# 19_DDR3_BOT.net
KiCad netlist of a schematic drawn in Altium Designer
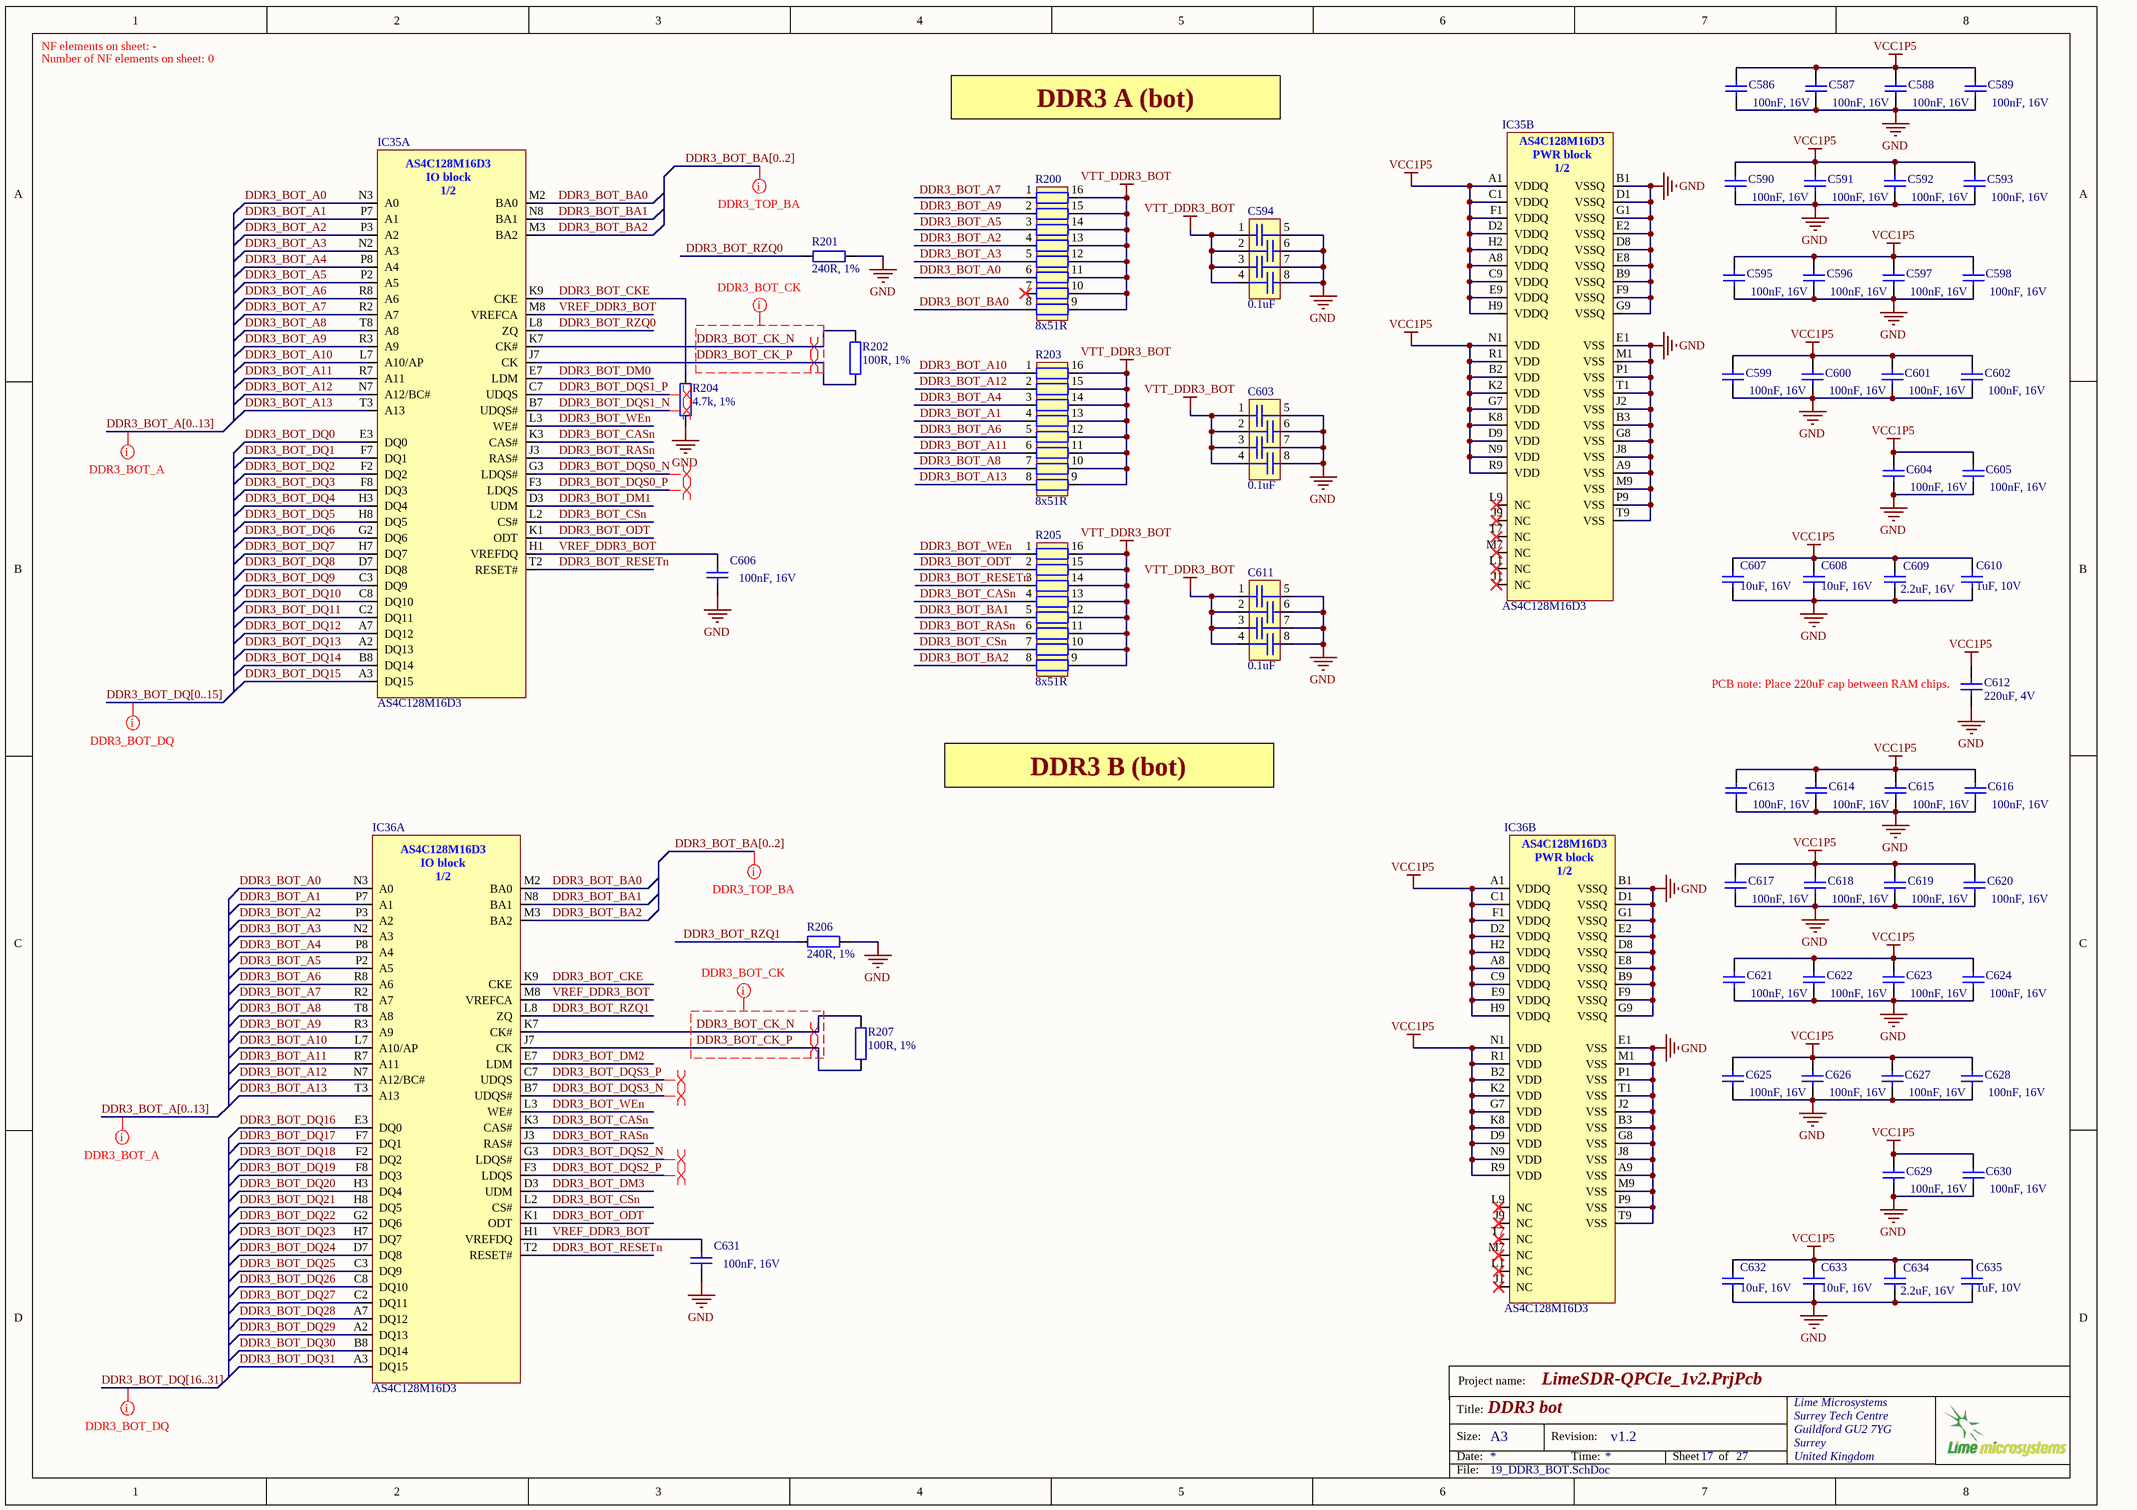
[diagram p0: 19_DDR3_BOT.SchDoc]

(export (version "E")
  (design (tool "Eeschema 10.0.6"))
  (components
    (comp (ref "C586")
      (value "100nF, 16V")
      (footprint "CAP0402")
      (fields
        (field (name "TOLERANCE") "10 %")
        (field (name "MANUFACTURER") "Murata Electronics")
        (field (name "MANUFACTURER PART NUMBER") "GRM155R71C104KA88D")
      )
      (libsource (lib "LimeFPGAboard_schLib") (part "Cap_0603"))
    )
    (comp (ref "C587")
      (value "100nF, 16V")
      (footprint "CAP0402")
      (fields
        (field (name "TOLERANCE") "10 %")
        (field (name "MANUFACTURER") "Murata Electronics")
        (field (name "MANUFACTURER PART NUMBER") "GRM155R71C104KA88D")
      )
      (libsource (lib "LimeFPGAboard_schLib") (part "Cap_0603"))
    )
    (comp (ref "C588")
      (value "100nF, 16V")
      (footprint "CAP0402")
      (fields
        (field (name "TOLERANCE") "10 %")
        (field (name "MANUFACTURER") "Murata Electronics")
        (field (name "MANUFACTURER PART NUMBER") "GRM155R71C104KA88D")
      )
      (libsource (lib "LimeFPGAboard_schLib") (part "Cap_0603"))
    )
    (comp (ref "C589")
      (value "100nF, 16V")
      (footprint "CAP0402")
      (fields
        (field (name "TOLERANCE") "10 %")
        (field (name "MANUFACTURER") "Murata Electronics")
        (field (name "MANUFACTURER PART NUMBER") "GRM155R71C104KA88D")
      )
      (libsource (lib "LimeFPGAboard_schLib") (part "Cap_0603"))
    )
    (comp (ref "C590")
      (value "100nF, 16V")
      (footprint "CAP0402")
      (fields
        (field (name "TOLERANCE") "10 %")
        (field (name "MANUFACTURER") "Murata Electronics")
        (field (name "MANUFACTURER PART NUMBER") "GRM155R71C104KA88D")
      )
      (libsource (lib "LimeFPGAboard_schLib") (part "Cap_0603"))
    )
    (comp (ref "C591")
      (value "100nF, 16V")
      (footprint "CAP0402")
      (fields
        (field (name "TOLERANCE") "10 %")
        (field (name "MANUFACTURER") "Murata Electronics")
        (field (name "MANUFACTURER PART NUMBER") "GRM155R71C104KA88D")
      )
      (libsource (lib "LimeFPGAboard_schLib") (part "Cap_0603"))
    )
    (comp (ref "C592")
      (value "100nF, 16V")
      (footprint "CAP0402")
      (fields
        (field (name "TOLERANCE") "10 %")
        (field (name "MANUFACTURER") "Murata Electronics")
        (field (name "MANUFACTURER PART NUMBER") "GRM155R71C104KA88D")
      )
      (libsource (lib "LimeFPGAboard_schLib") (part "Cap_0603"))
    )
    (comp (ref "C593")
      (value "100nF, 16V")
      (footprint "CAP0402")
      (fields
        (field (name "TOLERANCE") "10 %")
        (field (name "MANUFACTURER") "Murata Electronics")
        (field (name "MANUFACTURER PART NUMBER") "GRM155R71C104KA88D")
      )
      (libsource (lib "LimeFPGAboard_schLib") (part "Cap_0603"))
    )
    (comp (ref "C594")
      (value "0.1uF")
      (footprint "CKCA43X7R1C104M100AA")
      (fields (field (name "MANUFACTURER") "TDK") (field (name "TOLERANCE") "20 %"))
      (libsource (lib "LimeFPGAboard_schLib") (part "4X_cap_array_1206"))
    )
    (comp (ref "C595")
      (value "100nF, 16V")
      (footprint "CAP0402")
      (fields
        (field (name "TOLERANCE") "10 %")
        (field (name "MANUFACTURER") "Murata Electronics")
        (field (name "MANUFACTURER PART NUMBER") "GRM155R71C104KA88D")
      )
      (libsource (lib "LimeFPGAboard_schLib") (part "Cap_0603"))
    )
    (comp (ref "C596")
      (value "100nF, 16V")
      (footprint "CAP0402")
      (fields
        (field (name "TOLERANCE") "10 %")
        (field (name "MANUFACTURER") "Murata Electronics")
        (field (name "MANUFACTURER PART NUMBER") "GRM155R71C104KA88D")
      )
      (libsource (lib "LimeFPGAboard_schLib") (part "Cap_0603"))
    )
    (comp (ref "C597")
      (value "100nF, 16V")
      (footprint "CAP0402")
      (fields
        (field (name "TOLERANCE") "10 %")
        (field (name "MANUFACTURER") "Murata Electronics")
        (field (name "MANUFACTURER PART NUMBER") "GRM155R71C104KA88D")
      )
      (libsource (lib "LimeFPGAboard_schLib") (part "Cap_0603"))
    )
    (comp (ref "C598")
      (value "100nF, 16V")
      (footprint "CAP0402")
      (fields
        (field (name "TOLERANCE") "10 %")
        (field (name "MANUFACTURER") "Murata Electronics")
        (field (name "MANUFACTURER PART NUMBER") "GRM155R71C104KA88D")
      )
      (libsource (lib "LimeFPGAboard_schLib") (part "Cap_0603"))
    )
    (comp (ref "C599")
      (value "100nF, 16V")
      (footprint "CAP0402")
      (fields
        (field (name "TOLERANCE") "10 %")
        (field (name "MANUFACTURER") "Murata Electronics")
        (field (name "MANUFACTURER PART NUMBER") "GRM155R71C104KA88D")
      )
      (libsource (lib "LimeFPGAboard_schLib") (part "Cap_0603"))
    )
    (comp (ref "C600")
      (value "100nF, 16V")
      (footprint "CAP0402")
      (fields
        (field (name "TOLERANCE") "10 %")
        (field (name "MANUFACTURER") "Murata Electronics")
        (field (name "MANUFACTURER PART NUMBER") "GRM155R71C104KA88D")
      )
      (libsource (lib "LimeFPGAboard_schLib") (part "Cap_0603"))
    )
    (comp (ref "C601")
      (value "100nF, 16V")
      (footprint "CAP0402")
      (fields
        (field (name "TOLERANCE") "10 %")
        (field (name "MANUFACTURER") "Murata Electronics")
        (field (name "MANUFACTURER PART NUMBER") "GRM155R71C104KA88D")
      )
      (libsource (lib "LimeFPGAboard_schLib") (part "Cap_0603"))
    )
    (comp (ref "C602")
      (value "100nF, 16V")
      (footprint "CAP0402")
      (fields
        (field (name "TOLERANCE") "10 %")
        (field (name "MANUFACTURER") "Murata Electronics")
        (field (name "MANUFACTURER PART NUMBER") "GRM155R71C104KA88D")
      )
      (libsource (lib "LimeFPGAboard_schLib") (part "Cap_0603"))
    )
    (comp (ref "C603")
      (value "0.1uF")
      (footprint "CKCA43X7R1C104M100AA")
      (fields (field (name "MANUFACTURER") "TDK") (field (name "TOLERANCE") "20 %"))
      (libsource (lib "LimeFPGAboard_schLib") (part "4X_cap_array_1206"))
    )
    (comp (ref "C604")
      (value "100nF, 16V")
      (footprint "CAP0402")
      (fields
        (field (name "TOLERANCE") "10 %")
        (field (name "MANUFACTURER") "Murata Electronics")
        (field (name "MANUFACTURER PART NUMBER") "GRM155R71C104KA88D")
      )
      (libsource (lib "LimeFPGAboard_schLib") (part "Cap_0603"))
    )
    (comp (ref "C605")
      (value "100nF, 16V")
      (footprint "CAP0402")
      (fields
        (field (name "TOLERANCE") "10 %")
        (field (name "MANUFACTURER") "Murata Electronics")
        (field (name "MANUFACTURER PART NUMBER") "GRM155R71C104KA88D")
      )
      (libsource (lib "LimeFPGAboard_schLib") (part "Cap_0603"))
    )
    (comp (ref "C606")
      (value "100nF, 16V")
      (footprint "CAP0402")
      (fields
        (field (name "TOLERANCE") "10 %")
        (field (name "MANUFACTURER") "Murata Electronics")
        (field (name "MANUFACTURER PART NUMBER") "GRM155R71C104KA88D")
      )
      (libsource (lib "LimeFPGAboard_schLib") (part "Cap_0603"))
    )
    (comp (ref "C607")
      (value "10uF, 16V")
      (footprint "CAP0603")
      (fields (field (name "TOLERANCE") "±20%") (field (name "MANUFACTURER") "Yageo"))
      (libsource (lib "LimeFPGAboard_schLib") (part "Cap_0603"))
    )
    (comp (ref "C608")
      (value "10uF, 16V")
      (footprint "CAP0603")
      (fields (field (name "TOLERANCE") "±20%") (field (name "MANUFACTURER") "Yageo"))
      (libsource (lib "LimeFPGAboard_schLib") (part "Cap_0603"))
    )
    (comp (ref "C609")
      (value "2.2uF, 16V")
      (footprint "CAP0402")
      (description "CAP CER 2.2UF 16V 10% X5R 0402")
      (fields (field (name "TOLERANCE") "±10%") (field (name "MANUFACTURER") "TDK Corporation"))
      (libsource (lib "LimeFPGAboard_schLib") (part "Cap_0603"))
    )
    (comp (ref "C610")
      (value "1uF, 10V")
      (footprint "CAP0402")
      (fields (field (name "MANUFACTURER") "TDK"))
      (libsource (lib "LimeFPGAboard_schLib") (part "Cap_0603"))
    )
    (comp (ref "C611")
      (value "0.1uF")
      (footprint "CKCA43X7R1C104M100AA")
      (fields (field (name "MANUFACTURER") "TDK") (field (name "TOLERANCE") "20 %"))
      (libsource (lib "LimeFPGAboard_schLib") (part "4X_cap_array_1206"))
    )
    (comp (ref "C612")
      (value "220uF, 4V")
      (footprint "CAP1206")
      (fields
        (field (name "MANUFACTURER PART NUMBER") "GRM31CR60G227ME11L")
        (field (name "MANUFACTURER") "Murata Electronics North America")
        (field (name "TOLERANCE") "±20%")
      )
      (libsource (lib "LimeFPGAboard_schLib") (part "Cap_1206"))
    )
    (comp (ref "C613")
      (value "100nF, 16V")
      (footprint "CAP0402")
      (fields
        (field (name "TOLERANCE") "10 %")
        (field (name "MANUFACTURER") "Murata Electronics")
        (field (name "MANUFACTURER PART NUMBER") "GRM155R71C104KA88D")
      )
      (libsource (lib "LimeFPGAboard_schLib") (part "Cap_0603"))
    )
    (comp (ref "C614")
      (value "100nF, 16V")
      (footprint "CAP0402")
      (fields
        (field (name "TOLERANCE") "10 %")
        (field (name "MANUFACTURER") "Murata Electronics")
        (field (name "MANUFACTURER PART NUMBER") "GRM155R71C104KA88D")
      )
      (libsource (lib "LimeFPGAboard_schLib") (part "Cap_0603"))
    )
    (comp (ref "C615")
      (value "100nF, 16V")
      (footprint "CAP0402")
      (fields
        (field (name "TOLERANCE") "10 %")
        (field (name "MANUFACTURER") "Murata Electronics")
        (field (name "MANUFACTURER PART NUMBER") "GRM155R71C104KA88D")
      )
      (libsource (lib "LimeFPGAboard_schLib") (part "Cap_0603"))
    )
    (comp (ref "C616")
      (value "100nF, 16V")
      (footprint "CAP0402")
      (fields
        (field (name "TOLERANCE") "10 %")
        (field (name "MANUFACTURER") "Murata Electronics")
        (field (name "MANUFACTURER PART NUMBER") "GRM155R71C104KA88D")
      )
      (libsource (lib "LimeFPGAboard_schLib") (part "Cap_0603"))
    )
    (comp (ref "C617")
      (value "100nF, 16V")
      (footprint "CAP0402")
      (fields
        (field (name "TOLERANCE") "10 %")
        (field (name "MANUFACTURER") "Murata Electronics")
        (field (name "MANUFACTURER PART NUMBER") "GRM155R71C104KA88D")
      )
      (libsource (lib "LimeFPGAboard_schLib") (part "Cap_0603"))
    )
    (comp (ref "C618")
      (value "100nF, 16V")
      (footprint "CAP0402")
      (fields
        (field (name "TOLERANCE") "10 %")
        (field (name "MANUFACTURER") "Murata Electronics")
        (field (name "MANUFACTURER PART NUMBER") "GRM155R71C104KA88D")
      )
      (libsource (lib "LimeFPGAboard_schLib") (part "Cap_0603"))
    )
    (comp (ref "C619")
      (value "100nF, 16V")
      (footprint "CAP0402")
      (fields
        (field (name "TOLERANCE") "10 %")
        (field (name "MANUFACTURER") "Murata Electronics")
        (field (name "MANUFACTURER PART NUMBER") "GRM155R71C104KA88D")
      )
      (libsource (lib "LimeFPGAboard_schLib") (part "Cap_0603"))
    )
    (comp (ref "C620")
      (value "100nF, 16V")
      (footprint "CAP0402")
      (fields
        (field (name "TOLERANCE") "10 %")
        (field (name "MANUFACTURER") "Murata Electronics")
        (field (name "MANUFACTURER PART NUMBER") "GRM155R71C104KA88D")
      )
      (libsource (lib "LimeFPGAboard_schLib") (part "Cap_0603"))
    )
    (comp (ref "C621")
      (value "100nF, 16V")
      (footprint "CAP0402")
      (fields
        (field (name "TOLERANCE") "10 %")
        (field (name "MANUFACTURER") "Murata Electronics")
        (field (name "MANUFACTURER PART NUMBER") "GRM155R71C104KA88D")
      )
      (libsource (lib "LimeFPGAboard_schLib") (part "Cap_0603"))
    )
    (comp (ref "C622")
      (value "100nF, 16V")
      (footprint "CAP0402")
      (fields
        (field (name "TOLERANCE") "10 %")
        (field (name "MANUFACTURER") "Murata Electronics")
        (field (name "MANUFACTURER PART NUMBER") "GRM155R71C104KA88D")
      )
      (libsource (lib "LimeFPGAboard_schLib") (part "Cap_0603"))
    )
    (comp (ref "C623")
      (value "100nF, 16V")
      (footprint "CAP0402")
      (fields
        (field (name "TOLERANCE") "10 %")
        (field (name "MANUFACTURER") "Murata Electronics")
        (field (name "MANUFACTURER PART NUMBER") "GRM155R71C104KA88D")
      )
      (libsource (lib "LimeFPGAboard_schLib") (part "Cap_0603"))
    )
    (comp (ref "C624")
      (value "100nF, 16V")
      (footprint "CAP0402")
      (fields
        (field (name "TOLERANCE") "10 %")
        (field (name "MANUFACTURER") "Murata Electronics")
        (field (name "MANUFACTURER PART NUMBER") "GRM155R71C104KA88D")
      )
      (libsource (lib "LimeFPGAboard_schLib") (part "Cap_0603"))
    )
    (comp (ref "C625")
      (value "100nF, 16V")
      (footprint "CAP0402")
      (fields
        (field (name "TOLERANCE") "10 %")
        (field (name "MANUFACTURER") "Murata Electronics")
        (field (name "MANUFACTURER PART NUMBER") "GRM155R71C104KA88D")
      )
      (libsource (lib "LimeFPGAboard_schLib") (part "Cap_0603"))
    )
    (comp (ref "C626")
      (value "100nF, 16V")
      (footprint "CAP0402")
      (fields
        (field (name "TOLERANCE") "10 %")
        (field (name "MANUFACTURER") "Murata Electronics")
        (field (name "MANUFACTURER PART NUMBER") "GRM155R71C104KA88D")
      )
      (libsource (lib "LimeFPGAboard_schLib") (part "Cap_0603"))
    )
    (comp (ref "C627")
      (value "100nF, 16V")
      (footprint "CAP0402")
      (fields
        (field (name "TOLERANCE") "10 %")
        (field (name "MANUFACTURER") "Murata Electronics")
        (field (name "MANUFACTURER PART NUMBER") "GRM155R71C104KA88D")
      )
      (libsource (lib "LimeFPGAboard_schLib") (part "Cap_0603"))
    )
    (comp (ref "C628")
      (value "100nF, 16V")
      (footprint "CAP0402")
      (fields
        (field (name "TOLERANCE") "10 %")
        (field (name "MANUFACTURER") "Murata Electronics")
        (field (name "MANUFACTURER PART NUMBER") "GRM155R71C104KA88D")
      )
      (libsource (lib "LimeFPGAboard_schLib") (part "Cap_0603"))
    )
    (comp (ref "C629")
      (value "100nF, 16V")
      (footprint "CAP0402")
      (fields
        (field (name "TOLERANCE") "10 %")
        (field (name "MANUFACTURER") "Murata Electronics")
        (field (name "MANUFACTURER PART NUMBER") "GRM155R71C104KA88D")
      )
      (libsource (lib "LimeFPGAboard_schLib") (part "Cap_0603"))
    )
    (comp (ref "C630")
      (value "100nF, 16V")
      (footprint "CAP0402")
      (fields
        (field (name "TOLERANCE") "10 %")
        (field (name "MANUFACTURER") "Murata Electronics")
        (field (name "MANUFACTURER PART NUMBER") "GRM155R71C104KA88D")
      )
      (libsource (lib "LimeFPGAboard_schLib") (part "Cap_0603"))
    )
    (comp (ref "C631")
      (value "100nF, 16V")
      (footprint "CAP0402")
      (fields
        (field (name "TOLERANCE") "10 %")
        (field (name "MANUFACTURER") "Murata Electronics")
        (field (name "MANUFACTURER PART NUMBER") "GRM155R71C104KA88D")
      )
      (libsource (lib "LimeFPGAboard_schLib") (part "Cap_0603"))
    )
    (comp (ref "C632")
      (value "10uF, 16V")
      (footprint "CAP0603")
      (fields (field (name "TOLERANCE") "±20%") (field (name "MANUFACTURER") "Yageo"))
      (libsource (lib "LimeFPGAboard_schLib") (part "Cap_0603"))
    )
    (comp (ref "C633")
      (value "10uF, 16V")
      (footprint "CAP0603")
      (fields (field (name "TOLERANCE") "±20%") (field (name "MANUFACTURER") "Yageo"))
      (libsource (lib "LimeFPGAboard_schLib") (part "Cap_0603"))
    )
    (comp (ref "C634")
      (value "2.2uF, 16V")
      (footprint "CAP0402")
      (description "CAP CER 2.2UF 16V 10% X5R 0402")
      (fields (field (name "TOLERANCE") "±10%") (field (name "MANUFACTURER") "TDK Corporation"))
      (libsource (lib "LimeFPGAboard_schLib") (part "Cap_0603"))
    )
    (comp (ref "C635")
      (value "1uF, 10V")
      (footprint "CAP0402")
      (fields (field (name "MANUFACTURER") "TDK"))
      (libsource (lib "LimeFPGAboard_schLib") (part "Cap_0603"))
    )
    (comp (ref "IC35")
      (value "AS4C128M16D3")
      (footprint "AS4C128M16D3")
      (fields (field (name "MANUFACTURER") "Alliance Memory, Inc."))
      (libsource (lib "LimeFPGAboard_schLib") (part "AS4C128M16D3"))
    )
    (comp (ref "IC36")
      (value "AS4C128M16D3")
      (footprint "AS4C128M16D3")
      (fields (field (name "MANUFACTURER") "Alliance Memory, Inc."))
      (libsource (lib "LimeFPGAboard_schLib") (part "AS4C128M16D3"))
    )
    (comp (ref "R200")
      (value "8x51R")
      (footprint "EXB2HV")
      (fields
        (field (name "MANUFACTURER") "PANASONIC ELECTRONIC COMPONENTS")
        (field (name "MANUFACTURER_1") "Panasonic Electronic Components")
      )
      (libsource (lib "LimeFPGAboard_schLib") (part "8X_resistor_array_0402"))
    )
    (comp (ref "R201")
      (value "240R, 1%")
      (footprint "RES0402")
      (fields (field (name "TOLERANCE") "±1%") (field (name "MANUFACTURER") "Vishay Dale"))
      (libsource (lib "LimeFPGAboard_schLib") (part "Res_0402"))
    )
    (comp (ref "R202")
      (value "100R, 1%")
      (footprint "RES0402")
      (fields (field (name "TOLERANCE") "±1%") (field (name "MANUFACTURER") "Stackpole Electronics Inc."))
      (libsource (lib "LimeFPGAboard_schLib") (part "Res_0402"))
    )
    (comp (ref "R203")
      (value "8x51R")
      (footprint "EXB2HV")
      (fields
        (field (name "MANUFACTURER") "PANASONIC ELECTRONIC COMPONENTS")
        (field (name "MANUFACTURER_1") "Panasonic Electronic Components")
      )
      (libsource (lib "LimeFPGAboard_schLib") (part "8X_resistor_array_0402"))
    )
    (comp (ref "R204")
      (value "4.7k, 1%")
      (footprint "RES0402")
      (fields (field (name "MANUFACTURER") "Yageo") (field (name "TOLERANCE") "±1%"))
      (libsource (lib "LimeMicroAltiumLib_schLib") (part "Res_0402"))
    )
    (comp (ref "R205")
      (value "8x51R")
      (footprint "EXB2HV")
      (fields
        (field (name "MANUFACTURER") "PANASONIC ELECTRONIC COMPONENTS")
        (field (name "MANUFACTURER_1") "Panasonic Electronic Components")
      )
      (libsource (lib "LimeFPGAboard_schLib") (part "8X_resistor_array_0402"))
    )
    (comp (ref "R206")
      (value "240R, 1%")
      (footprint "RES0402")
      (fields (field (name "TOLERANCE") "±1%") (field (name "MANUFACTURER") "Vishay Dale"))
      (libsource (lib "LimeFPGAboard_schLib") (part "Res_0402"))
    )
    (comp (ref "R207")
      (value "100R, 1%")
      (footprint "RES0402")
      (fields (field (name "TOLERANCE") "±1%") (field (name "MANUFACTURER") "Stackpole Electronics Inc."))
      (libsource (lib "LimeFPGAboard_schLib") (part "Res_0402"))
    )
  )
  (nets
    (net (code "1") (name "/DDR3_BOT_A0") (class "Default")
      (node (ref "IC35") (pin "N3") (pinfunction "A0_N3") (pintype "passive"))
      (node (ref "IC36") (pin "N3") (pinfunction "A0_N3") (pintype "passive"))
      (node (ref "R200") (pin "6") (pinfunction "6_6") (pintype "passive"))
    )
    (net (code "2") (name "/DDR3_BOT_A1") (class "Default")
      (node (ref "IC35") (pin "P7") (pinfunction "A1_P7") (pintype "passive"))
      (node (ref "IC36") (pin "P7") (pinfunction "A1_P7") (pintype "passive"))
      (node (ref "R203") (pin "4") (pinfunction "4_4") (pintype "passive"))
    )
    (net (code "3") (name "/DDR3_BOT_A2") (class "Default")
      (node (ref "IC35") (pin "P3") (pinfunction "A2_P3") (pintype "passive"))
      (node (ref "IC36") (pin "P3") (pinfunction "A2_P3") (pintype "passive"))
      (node (ref "R200") (pin "4") (pinfunction "4_4") (pintype "passive"))
    )
    (net (code "4") (name "/DDR3_BOT_A3") (class "Default")
      (node (ref "IC35") (pin "N2") (pinfunction "A3_N2") (pintype "passive"))
      (node (ref "IC36") (pin "N2") (pinfunction "A3_N2") (pintype "passive"))
      (node (ref "R200") (pin "5") (pinfunction "5_5") (pintype "passive"))
    )
    (net (code "5") (name "/DDR3_BOT_A4") (class "Default")
      (node (ref "IC35") (pin "P8") (pinfunction "A4_P8") (pintype "passive"))
      (node (ref "IC36") (pin "P8") (pinfunction "A4_P8") (pintype "passive"))
      (node (ref "R203") (pin "3") (pinfunction "3_3") (pintype "passive"))
    )
    (net (code "6") (name "/DDR3_BOT_A5") (class "Default")
      (node (ref "IC35") (pin "P2") (pinfunction "A5_P2") (pintype "passive"))
      (node (ref "IC36") (pin "P2") (pinfunction "A5_P2") (pintype "passive"))
      (node (ref "R200") (pin "3") (pinfunction "3_3") (pintype "passive"))
    )
    (net (code "7") (name "/DDR3_BOT_A6") (class "Default")
      (node (ref "IC35") (pin "R8") (pinfunction "A6_R8") (pintype "passive"))
      (node (ref "IC36") (pin "R8") (pinfunction "A6_R8") (pintype "passive"))
      (node (ref "R203") (pin "5") (pinfunction "5_5") (pintype "passive"))
    )
    (net (code "8") (name "/DDR3_BOT_A7") (class "Default")
      (node (ref "IC35") (pin "R2") (pinfunction "A7_R2") (pintype "passive"))
      (node (ref "IC36") (pin "R2") (pinfunction "A7_R2") (pintype "passive"))
      (node (ref "R200") (pin "1") (pinfunction "1_1") (pintype "passive"))
    )
    (net (code "9") (name "/DDR3_BOT_A8") (class "Default")
      (node (ref "IC35") (pin "T8") (pinfunction "A8_T8") (pintype "passive"))
      (node (ref "IC36") (pin "T8") (pinfunction "A8_T8") (pintype "passive"))
      (node (ref "R203") (pin "7") (pinfunction "7_7") (pintype "passive"))
    )
    (net (code "10") (name "/DDR3_BOT_A9") (class "Default")
      (node (ref "IC35") (pin "R3") (pinfunction "A9_R3") (pintype "passive"))
      (node (ref "IC36") (pin "R3") (pinfunction "A9_R3") (pintype "passive"))
      (node (ref "R200") (pin "2") (pinfunction "2_2") (pintype "passive"))
    )
    (net (code "11") (name "/DDR3_BOT_A10") (class "Default")
      (node (ref "IC35") (pin "L7") (pinfunction "A10/AP_L7") (pintype "passive"))
      (node (ref "IC36") (pin "L7") (pinfunction "A10/AP_L7") (pintype "passive"))
      (node (ref "R203") (pin "1") (pinfunction "1_1") (pintype "passive"))
    )
    (net (code "12") (name "/DDR3_BOT_A11") (class "Default")
      (node (ref "IC35") (pin "R7") (pinfunction "A11_R7") (pintype "passive"))
      (node (ref "IC36") (pin "R7") (pinfunction "A11_R7") (pintype "passive"))
      (node (ref "R203") (pin "6") (pinfunction "6_6") (pintype "passive"))
    )
    (net (code "13") (name "/DDR3_BOT_A12") (class "Default")
      (node (ref "IC35") (pin "N7") (pinfunction "A12/BC#_N7") (pintype "passive"))
      (node (ref "IC36") (pin "N7") (pinfunction "A12/BC#_N7") (pintype "passive"))
      (node (ref "R203") (pin "2") (pinfunction "2_2") (pintype "passive"))
    )
    (net (code "14") (name "/DDR3_BOT_A13") (class "Default")
      (node (ref "IC35") (pin "T3") (pinfunction "A13_T3") (pintype "passive"))
      (node (ref "IC36") (pin "T3") (pinfunction "A13_T3") (pintype "passive"))
      (node (ref "R203") (pin "8") (pinfunction "8_8") (pintype "passive"))
    )
    (net (code "16") (name "/DDR3_BOT_BA0") (class "Default")
      (node (ref "IC35") (pin "M2") (pinfunction "BA0_M2") (pintype "passive"))
      (node (ref "IC36") (pin "M2") (pinfunction "BA0_M2") (pintype "passive"))
      (node (ref "R200") (pin "8") (pinfunction "8_8") (pintype "passive"))
    )
    (net (code "17") (name "/DDR3_BOT_BA1") (class "Default")
      (node (ref "IC35") (pin "N8") (pinfunction "BA1_N8") (pintype "passive"))
      (node (ref "IC36") (pin "N8") (pinfunction "BA1_N8") (pintype "passive"))
      (node (ref "R205") (pin "5") (pinfunction "5_5") (pintype "passive"))
    )
    (net (code "18") (name "/DDR3_BOT_BA2") (class "Default")
      (node (ref "IC35") (pin "M3") (pinfunction "BA2_M3") (pintype "passive"))
      (node (ref "IC36") (pin "M3") (pinfunction "BA2_M3") (pintype "passive"))
      (node (ref "R205") (pin "8") (pinfunction "8_8") (pintype "passive"))
    )
    (net (code "20") (name "/DDR3_BOT_CASn") (class "Default")
      (node (ref "IC35") (pin "K3") (pinfunction "CAS#_K3") (pintype "passive"))
      (node (ref "IC36") (pin "K3") (pinfunction "CAS#_K3") (pintype "passive"))
      (node (ref "R205") (pin "4") (pinfunction "4_4") (pintype "passive"))
    )
    (net (code "21") (name "/DDR3_BOT_CKE") (class "Default")
      (node (ref "IC35") (pin "K9") (pinfunction "CKE_K9") (pintype "passive"))
      (node (ref "IC36") (pin "K9") (pinfunction "CKE_K9") (pintype "passive"))
      (node (ref "R204") (pin "1") (pinfunction "1_1") (pintype "passive"))
    )
    (net (code "22") (name "/DDR3_BOT_CK_N") (class "Default")
      (node (ref "IC35") (pin "K7") (pinfunction "CK#_K7") (pintype "passive"))
      (node (ref "IC36") (pin "K7") (pinfunction "CK#_K7") (pintype "passive"))
      (node (ref "R202") (pin "2") (pinfunction "2_2") (pintype "passive"))
      (node (ref "R207") (pin "2") (pinfunction "2_2") (pintype "passive"))
    )
    (net (code "23") (name "/DDR3_BOT_CK_P") (class "Default")
      (node (ref "IC35") (pin "J7") (pinfunction "CK_J7") (pintype "passive"))
      (node (ref "IC36") (pin "J7") (pinfunction "CK_J7") (pintype "passive"))
      (node (ref "R202") (pin "1") (pinfunction "1_1") (pintype "passive"))
      (node (ref "R207") (pin "1") (pinfunction "1_1") (pintype "passive"))
    )
    (net (code "24") (name "/DDR3_BOT_CSn") (class "Default")
      (node (ref "IC35") (pin "L2") (pinfunction "CS#_L2") (pintype "passive"))
      (node (ref "IC36") (pin "L2") (pinfunction "CS#_L2") (pintype "passive"))
      (node (ref "R205") (pin "7") (pinfunction "7_7") (pintype "passive"))
    )
    (net (code "25") (name "/DDR3_BOT_DM0") (class "Default")
      (node (ref "IC35") (pin "E7") (pinfunction "LDM_E7") (pintype "passive"))
    )
    (net (code "26") (name "/DDR3_BOT_DM1") (class "Default")
      (node (ref "IC35") (pin "D3") (pinfunction "UDM_D3") (pintype "passive"))
    )
    (net (code "27") (name "/DDR3_BOT_DM2") (class "Default")
      (node (ref "IC36") (pin "E7") (pinfunction "LDM_E7") (pintype "passive"))
    )
    (net (code "28") (name "/DDR3_BOT_DM3") (class "Default")
      (node (ref "IC36") (pin "D3") (pinfunction "UDM_D3") (pintype "passive"))
    )
    (net (code "29") (name "/DDR3_BOT_DQ0") (class "Default")
      (node (ref "IC35") (pin "E3") (pinfunction "DQ0_E3") (pintype "passive"))
    )
    (net (code "30") (name "/DDR3_BOT_DQ1") (class "Default")
      (node (ref "IC35") (pin "F7") (pinfunction "DQ1_F7") (pintype "passive"))
    )
    (net (code "31") (name "/DDR3_BOT_DQ2") (class "Default")
      (node (ref "IC35") (pin "F2") (pinfunction "DQ2_F2") (pintype "passive"))
    )
    (net (code "32") (name "/DDR3_BOT_DQ3") (class "Default")
      (node (ref "IC35") (pin "F8") (pinfunction "DQ3_F8") (pintype "passive"))
    )
    (net (code "33") (name "/DDR3_BOT_DQ4") (class "Default")
      (node (ref "IC35") (pin "H3") (pinfunction "DQ4_H3") (pintype "passive"))
    )
    (net (code "34") (name "/DDR3_BOT_DQ5") (class "Default")
      (node (ref "IC35") (pin "H8") (pinfunction "DQ5_H8") (pintype "passive"))
    )
    (net (code "35") (name "/DDR3_BOT_DQ6") (class "Default")
      (node (ref "IC35") (pin "G2") (pinfunction "DQ6_G2") (pintype "passive"))
    )
    (net (code "36") (name "/DDR3_BOT_DQ7") (class "Default")
      (node (ref "IC35") (pin "H7") (pinfunction "DQ7_H7") (pintype "passive"))
    )
    (net (code "37") (name "/DDR3_BOT_DQ8") (class "Default")
      (node (ref "IC35") (pin "D7") (pinfunction "DQ8_D7") (pintype "passive"))
    )
    (net (code "38") (name "/DDR3_BOT_DQ9") (class "Default")
      (node (ref "IC35") (pin "C3") (pinfunction "DQ9_C3") (pintype "passive"))
    )
    (net (code "39") (name "/DDR3_BOT_DQ10") (class "Default")
      (node (ref "IC35") (pin "C8") (pinfunction "DQ10_C8") (pintype "passive"))
    )
    (net (code "40") (name "/DDR3_BOT_DQ11") (class "Default")
      (node (ref "IC35") (pin "C2") (pinfunction "DQ11_C2") (pintype "passive"))
    )
    (net (code "41") (name "/DDR3_BOT_DQ12") (class "Default")
      (node (ref "IC35") (pin "A7") (pinfunction "DQ12_A7") (pintype "passive"))
    )
    (net (code "42") (name "/DDR3_BOT_DQ13") (class "Default")
      (node (ref "IC35") (pin "A2") (pinfunction "DQ13_A2") (pintype "passive"))
    )
    (net (code "43") (name "/DDR3_BOT_DQ14") (class "Default")
      (node (ref "IC35") (pin "B8") (pinfunction "DQ14_B8") (pintype "passive"))
    )
    (net (code "44") (name "/DDR3_BOT_DQ15") (class "Default")
      (node (ref "IC35") (pin "A3") (pinfunction "DQ15_A3") (pintype "passive"))
    )
    (net (code "45") (name "/DDR3_BOT_DQ16") (class "Default")
      (node (ref "IC36") (pin "E3") (pinfunction "DQ0_E3") (pintype "passive"))
    )
    (net (code "46") (name "/DDR3_BOT_DQ17") (class "Default")
      (node (ref "IC36") (pin "F7") (pinfunction "DQ1_F7") (pintype "passive"))
    )
    (net (code "47") (name "/DDR3_BOT_DQ18") (class "Default")
      (node (ref "IC36") (pin "F2") (pinfunction "DQ2_F2") (pintype "passive"))
    )
    (net (code "48") (name "/DDR3_BOT_DQ19") (class "Default")
      (node (ref "IC36") (pin "F8") (pinfunction "DQ3_F8") (pintype "passive"))
    )
    (net (code "49") (name "/DDR3_BOT_DQ20") (class "Default")
      (node (ref "IC36") (pin "H3") (pinfunction "DQ4_H3") (pintype "passive"))
    )
    (net (code "50") (name "/DDR3_BOT_DQ21") (class "Default")
      (node (ref "IC36") (pin "H8") (pinfunction "DQ5_H8") (pintype "passive"))
    )
    (net (code "51") (name "/DDR3_BOT_DQ22") (class "Default")
      (node (ref "IC36") (pin "G2") (pinfunction "DQ6_G2") (pintype "passive"))
    )
    (net (code "52") (name "/DDR3_BOT_DQ23") (class "Default")
      (node (ref "IC36") (pin "H7") (pinfunction "DQ7_H7") (pintype "passive"))
    )
    (net (code "53") (name "/DDR3_BOT_DQ24") (class "Default")
      (node (ref "IC36") (pin "D7") (pinfunction "DQ8_D7") (pintype "passive"))
    )
    (net (code "54") (name "/DDR3_BOT_DQ25") (class "Default")
      (node (ref "IC36") (pin "C3") (pinfunction "DQ9_C3") (pintype "passive"))
    )
    (net (code "55") (name "/DDR3_BOT_DQ26") (class "Default")
      (node (ref "IC36") (pin "C8") (pinfunction "DQ10_C8") (pintype "passive"))
    )
    (net (code "56") (name "/DDR3_BOT_DQ27") (class "Default")
      (node (ref "IC36") (pin "C2") (pinfunction "DQ11_C2") (pintype "passive"))
    )
    (net (code "57") (name "/DDR3_BOT_DQ28") (class "Default")
      (node (ref "IC36") (pin "A7") (pinfunction "DQ12_A7") (pintype "passive"))
    )
    (net (code "58") (name "/DDR3_BOT_DQ29") (class "Default")
      (node (ref "IC36") (pin "A2") (pinfunction "DQ13_A2") (pintype "passive"))
    )
    (net (code "59") (name "/DDR3_BOT_DQ30") (class "Default")
      (node (ref "IC36") (pin "B8") (pinfunction "DQ14_B8") (pintype "passive"))
    )
    (net (code "60") (name "/DDR3_BOT_DQ31") (class "Default")
      (node (ref "IC36") (pin "A3") (pinfunction "DQ15_A3") (pintype "passive"))
    )
    (net (code "61") (name "/DDR3_BOT_DQS0_N") (class "Default")
      (node (ref "IC35") (pin "G3") (pinfunction "LDQS#_G3") (pintype "passive"))
    )
    (net (code "62") (name "/DDR3_BOT_DQS0_P") (class "Default")
      (node (ref "IC35") (pin "F3") (pinfunction "LDQS_F3") (pintype "passive"))
    )
    (net (code "63") (name "/DDR3_BOT_DQS1_N") (class "Default")
      (node (ref "IC35") (pin "B7") (pinfunction "UDQS#_B7") (pintype "passive"))
    )
    (net (code "64") (name "/DDR3_BOT_DQS1_P") (class "Default")
      (node (ref "IC35") (pin "C7") (pinfunction "UDQS_C7") (pintype "passive"))
    )
    (net (code "65") (name "/DDR3_BOT_DQS2_N") (class "Default")
      (node (ref "IC36") (pin "G3") (pinfunction "LDQS#_G3") (pintype "passive"))
    )
    (net (code "66") (name "/DDR3_BOT_DQS2_P") (class "Default")
      (node (ref "IC36") (pin "F3") (pinfunction "LDQS_F3") (pintype "passive"))
    )
    (net (code "67") (name "/DDR3_BOT_DQS3_N") (class "Default")
      (node (ref "IC36") (pin "B7") (pinfunction "UDQS#_B7") (pintype "passive"))
    )
    (net (code "68") (name "/DDR3_BOT_DQS3_P") (class "Default")
      (node (ref "IC36") (pin "C7") (pinfunction "UDQS_C7") (pintype "passive"))
    )
    (net (code "71") (name "/DDR3_BOT_ODT") (class "Default")
      (node (ref "IC35") (pin "K1") (pinfunction "ODT_K1") (pintype "passive"))
      (node (ref "IC36") (pin "K1") (pinfunction "ODT_K1") (pintype "passive"))
      (node (ref "R205") (pin "2") (pinfunction "2_2") (pintype "passive"))
    )
    (net (code "72") (name "/DDR3_BOT_RASn") (class "Default")
      (node (ref "IC35") (pin "J3") (pinfunction "RAS#_J3") (pintype "passive"))
      (node (ref "IC36") (pin "J3") (pinfunction "RAS#_J3") (pintype "passive"))
      (node (ref "R205") (pin "6") (pinfunction "6_6") (pintype "passive"))
    )
    (net (code "73") (name "/DDR3_BOT_RESETn") (class "Default")
      (node (ref "IC35") (pin "T2") (pinfunction "RESET#_T2") (pintype "passive"))
      (node (ref "IC36") (pin "T2") (pinfunction "RESET#_T2") (pintype "passive"))
      (node (ref "R205") (pin "3") (pinfunction "3_3") (pintype "passive"))
    )
    (net (code "74") (name "/DDR3_BOT_RZQ0") (class "Default")
      (node (ref "IC35") (pin "L8") (pinfunction "ZQ_L8") (pintype "passive"))
      (node (ref "R201") (pin "1") (pinfunction "1_1") (pintype "passive"))
    )
    (net (code "75") (name "/DDR3_BOT_RZQ1") (class "Default")
      (node (ref "IC36") (pin "L8") (pinfunction "ZQ_L8") (pintype "passive"))
      (node (ref "R206") (pin "1") (pinfunction "1_1") (pintype "passive"))
    )
    (net (code "76") (name "/DDR3_BOT_WEn") (class "Default")
      (node (ref "IC35") (pin "L3") (pinfunction "WE#_L3") (pintype "passive"))
      (node (ref "IC36") (pin "L3") (pinfunction "WE#_L3") (pintype "passive"))
      (node (ref "R205") (pin "1") (pinfunction "1_1") (pintype "passive"))
    )
    (net (code "77") (name "/VREF_DDR3_BOT") (class "Default")
      (node (ref "C606") (pin "1") (pinfunction "1_1") (pintype "passive"))
      (node (ref "C631") (pin "1") (pinfunction "1_1") (pintype "passive"))
      (node (ref "IC35") (pin "H1") (pinfunction "VREFDQ_H1") (pintype "passive"))
      (node (ref "IC35") (pin "M8") (pinfunction "VREFCA_M8") (pintype "passive"))
      (node (ref "IC36") (pin "H1") (pinfunction "VREFDQ_H1") (pintype "passive"))
      (node (ref "IC36") (pin "M8") (pinfunction "VREFCA_M8") (pintype "passive"))
    )
    (net (code "78") (name "GND") (class "Default")
      (node (ref "C586") (pin "2") (pinfunction "2_2") (pintype "passive"))
      (node (ref "C587") (pin "2") (pinfunction "2_2") (pintype "passive"))
      (node (ref "C588") (pin "2") (pinfunction "2_2") (pintype "passive"))
      (node (ref "C589") (pin "2") (pinfunction "2_2") (pintype "passive"))
      (node (ref "C590") (pin "2") (pinfunction "2_2") (pintype "passive"))
      (node (ref "C591") (pin "2") (pinfunction "2_2") (pintype "passive"))
      (node (ref "C592") (pin "2") (pinfunction "2_2") (pintype "passive"))
      (node (ref "C593") (pin "2") (pinfunction "2_2") (pintype "passive"))
      (node (ref "C594") (pin "5") (pinfunction "5_5") (pintype "passive"))
      (node (ref "C594") (pin "6") (pinfunction "6_6") (pintype "passive"))
      (node (ref "C594") (pin "7") (pinfunction "7_7") (pintype "passive"))
      (node (ref "C594") (pin "8") (pinfunction "8_8") (pintype "passive"))
      (node (ref "C595") (pin "2") (pinfunction "2_2") (pintype "passive"))
      (node (ref "C596") (pin "2") (pinfunction "2_2") (pintype "passive"))
      (node (ref "C597") (pin "2") (pinfunction "2_2") (pintype "passive"))
      (node (ref "C598") (pin "2") (pinfunction "2_2") (pintype "passive"))
      (node (ref "C599") (pin "2") (pinfunction "2_2") (pintype "passive"))
      (node (ref "C600") (pin "2") (pinfunction "2_2") (pintype "passive"))
      (node (ref "C601") (pin "2") (pinfunction "2_2") (pintype "passive"))
      (node (ref "C602") (pin "2") (pinfunction "2_2") (pintype "passive"))
      (node (ref "C603") (pin "5") (pinfunction "5_5") (pintype "passive"))
      (node (ref "C603") (pin "6") (pinfunction "6_6") (pintype "passive"))
      (node (ref "C603") (pin "7") (pinfunction "7_7") (pintype "passive"))
      (node (ref "C603") (pin "8") (pinfunction "8_8") (pintype "passive"))
      (node (ref "C604") (pin "2") (pinfunction "2_2") (pintype "passive"))
      (node (ref "C605") (pin "2") (pinfunction "2_2") (pintype "passive"))
      (node (ref "C606") (pin "2") (pinfunction "2_2") (pintype "passive"))
      (node (ref "C607") (pin "1") (pinfunction "1_1") (pintype "passive"))
      (node (ref "C608") (pin "1") (pinfunction "1_1") (pintype "passive"))
      (node (ref "C609") (pin "2") (pinfunction "2_2") (pintype "passive"))
      (node (ref "C610") (pin "1") (pinfunction "1_1") (pintype "passive"))
      (node (ref "C611") (pin "5") (pinfunction "5_5") (pintype "passive"))
      (node (ref "C611") (pin "6") (pinfunction "6_6") (pintype "passive"))
      (node (ref "C611") (pin "7") (pinfunction "7_7") (pintype "passive"))
      (node (ref "C611") (pin "8") (pinfunction "8_8") (pintype "passive"))
      (node (ref "C612") (pin "1") (pinfunction "1_1") (pintype "passive"))
      (node (ref "C613") (pin "2") (pinfunction "2_2") (pintype "passive"))
      (node (ref "C614") (pin "2") (pinfunction "2_2") (pintype "passive"))
      (node (ref "C615") (pin "2") (pinfunction "2_2") (pintype "passive"))
      (node (ref "C616") (pin "2") (pinfunction "2_2") (pintype "passive"))
      (node (ref "C617") (pin "2") (pinfunction "2_2") (pintype "passive"))
      (node (ref "C618") (pin "2") (pinfunction "2_2") (pintype "passive"))
      (node (ref "C619") (pin "2") (pinfunction "2_2") (pintype "passive"))
      (node (ref "C620") (pin "2") (pinfunction "2_2") (pintype "passive"))
      (node (ref "C621") (pin "2") (pinfunction "2_2") (pintype "passive"))
      (node (ref "C622") (pin "2") (pinfunction "2_2") (pintype "passive"))
      (node (ref "C623") (pin "2") (pinfunction "2_2") (pintype "passive"))
      (node (ref "C624") (pin "2") (pinfunction "2_2") (pintype "passive"))
      (node (ref "C625") (pin "2") (pinfunction "2_2") (pintype "passive"))
      (node (ref "C626") (pin "2") (pinfunction "2_2") (pintype "passive"))
      (node (ref "C627") (pin "2") (pinfunction "2_2") (pintype "passive"))
      (node (ref "C628") (pin "2") (pinfunction "2_2") (pintype "passive"))
      (node (ref "C629") (pin "2") (pinfunction "2_2") (pintype "passive"))
      (node (ref "C630") (pin "2") (pinfunction "2_2") (pintype "passive"))
      (node (ref "C631") (pin "2") (pinfunction "2_2") (pintype "passive"))
      (node (ref "C632") (pin "1") (pinfunction "1_1") (pintype "passive"))
      (node (ref "C633") (pin "1") (pinfunction "1_1") (pintype "passive"))
      (node (ref "C634") (pin "2") (pinfunction "2_2") (pintype "passive"))
      (node (ref "C635") (pin "1") (pinfunction "1_1") (pintype "passive"))
      (node (ref "IC35") (pin "A9") (pinfunction "VSS_A9") (pintype "power_in"))
      (node (ref "IC35") (pin "B1") (pinfunction "VSSQ_B1") (pintype "power_in"))
      (node (ref "IC35") (pin "B3") (pinfunction "VSS_B3") (pintype "power_in"))
      (node (ref "IC35") (pin "B9") (pinfunction "VSSQ_B9") (pintype "power_in"))
      (node (ref "IC35") (pin "D1") (pinfunction "VSSQ_D1") (pintype "power_in"))
      (node (ref "IC35") (pin "D8") (pinfunction "VSSQ_D8") (pintype "power_in"))
      (node (ref "IC35") (pin "E1") (pinfunction "VSS_E1") (pintype "power_in"))
      (node (ref "IC35") (pin "E2") (pinfunction "VSSQ_E2") (pintype "power_in"))
      (node (ref "IC35") (pin "E8") (pinfunction "VSSQ_E8") (pintype "power_in"))
      (node (ref "IC35") (pin "F9") (pinfunction "VSSQ_F9") (pintype "power_in"))
      (node (ref "IC35") (pin "G1") (pinfunction "VSSQ_G1") (pintype "power_in"))
      (node (ref "IC35") (pin "G8") (pinfunction "VSS_G8") (pintype "power_in"))
      (node (ref "IC35") (pin "G9") (pinfunction "VSSQ_G9") (pintype "power_in"))
      (node (ref "IC35") (pin "J2") (pinfunction "VSS_J2") (pintype "power_in"))
      (node (ref "IC35") (pin "J8") (pinfunction "VSS_J8") (pintype "power_in"))
      (node (ref "IC35") (pin "M1") (pinfunction "VSS_M1") (pintype "power_in"))
      (node (ref "IC35") (pin "M9") (pinfunction "VSS_M9") (pintype "power_in"))
      (node (ref "IC35") (pin "P1") (pinfunction "VSS_P1") (pintype "power_in"))
      (node (ref "IC35") (pin "P9") (pinfunction "VSS_P9") (pintype "power_in"))
      (node (ref "IC35") (pin "T1") (pinfunction "VSS_T1") (pintype "power_in"))
      (node (ref "IC35") (pin "T9") (pinfunction "VSS_T9") (pintype "power_in"))
      (node (ref "IC36") (pin "A9") (pinfunction "VSS_A9") (pintype "power_in"))
      (node (ref "IC36") (pin "B1") (pinfunction "VSSQ_B1") (pintype "power_in"))
      (node (ref "IC36") (pin "B3") (pinfunction "VSS_B3") (pintype "power_in"))
      (node (ref "IC36") (pin "B9") (pinfunction "VSSQ_B9") (pintype "power_in"))
      (node (ref "IC36") (pin "D1") (pinfunction "VSSQ_D1") (pintype "power_in"))
      (node (ref "IC36") (pin "D8") (pinfunction "VSSQ_D8") (pintype "power_in"))
      (node (ref "IC36") (pin "E1") (pinfunction "VSS_E1") (pintype "power_in"))
      (node (ref "IC36") (pin "E2") (pinfunction "VSSQ_E2") (pintype "power_in"))
      (node (ref "IC36") (pin "E8") (pinfunction "VSSQ_E8") (pintype "power_in"))
      (node (ref "IC36") (pin "F9") (pinfunction "VSSQ_F9") (pintype "power_in"))
      (node (ref "IC36") (pin "G1") (pinfunction "VSSQ_G1") (pintype "power_in"))
      (node (ref "IC36") (pin "G8") (pinfunction "VSS_G8") (pintype "power_in"))
      (node (ref "IC36") (pin "G9") (pinfunction "VSSQ_G9") (pintype "power_in"))
      (node (ref "IC36") (pin "J2") (pinfunction "VSS_J2") (pintype "power_in"))
      (node (ref "IC36") (pin "J8") (pinfunction "VSS_J8") (pintype "power_in"))
      (node (ref "IC36") (pin "M1") (pinfunction "VSS_M1") (pintype "power_in"))
      (node (ref "IC36") (pin "M9") (pinfunction "VSS_M9") (pintype "power_in"))
      (node (ref "IC36") (pin "P1") (pinfunction "VSS_P1") (pintype "power_in"))
      (node (ref "IC36") (pin "P9") (pinfunction "VSS_P9") (pintype "power_in"))
      (node (ref "IC36") (pin "T1") (pinfunction "VSS_T1") (pintype "power_in"))
      (node (ref "IC36") (pin "T9") (pinfunction "VSS_T9") (pintype "power_in"))
      (node (ref "R201") (pin "2") (pinfunction "2_2") (pintype "passive"))
      (node (ref "R204") (pin "2") (pinfunction "2_2") (pintype "passive"))
      (node (ref "R206") (pin "2") (pinfunction "2_2") (pintype "passive"))
    )
    (net (code "79") (name "VCC1P5") (class "Default")
      (node (ref "C586") (pin "1") (pinfunction "1_1") (pintype "passive"))
      (node (ref "C587") (pin "1") (pinfunction "1_1") (pintype "passive"))
      (node (ref "C588") (pin "1") (pinfunction "1_1") (pintype "passive"))
      (node (ref "C589") (pin "1") (pinfunction "1_1") (pintype "passive"))
      (node (ref "C590") (pin "1") (pinfunction "1_1") (pintype "passive"))
      (node (ref "C591") (pin "1") (pinfunction "1_1") (pintype "passive"))
      (node (ref "C592") (pin "1") (pinfunction "1_1") (pintype "passive"))
      (node (ref "C593") (pin "1") (pinfunction "1_1") (pintype "passive"))
      (node (ref "C595") (pin "1") (pinfunction "1_1") (pintype "passive"))
      (node (ref "C596") (pin "1") (pinfunction "1_1") (pintype "passive"))
      (node (ref "C597") (pin "1") (pinfunction "1_1") (pintype "passive"))
      (node (ref "C598") (pin "1") (pinfunction "1_1") (pintype "passive"))
      (node (ref "C599") (pin "1") (pinfunction "1_1") (pintype "passive"))
      (node (ref "C600") (pin "1") (pinfunction "1_1") (pintype "passive"))
      (node (ref "C601") (pin "1") (pinfunction "1_1") (pintype "passive"))
      (node (ref "C602") (pin "1") (pinfunction "1_1") (pintype "passive"))
      (node (ref "C604") (pin "1") (pinfunction "1_1") (pintype "passive"))
      (node (ref "C605") (pin "1") (pinfunction "1_1") (pintype "passive"))
      (node (ref "C607") (pin "2") (pinfunction "2_2") (pintype "passive"))
      (node (ref "C608") (pin "2") (pinfunction "2_2") (pintype "passive"))
      (node (ref "C609") (pin "1") (pinfunction "1_1") (pintype "passive"))
      (node (ref "C610") (pin "2") (pinfunction "2_2") (pintype "passive"))
      (node (ref "C612") (pin "2") (pinfunction "2_2") (pintype "passive"))
      (node (ref "C613") (pin "1") (pinfunction "1_1") (pintype "passive"))
      (node (ref "C614") (pin "1") (pinfunction "1_1") (pintype "passive"))
      (node (ref "C615") (pin "1") (pinfunction "1_1") (pintype "passive"))
      (node (ref "C616") (pin "1") (pinfunction "1_1") (pintype "passive"))
      (node (ref "C617") (pin "1") (pinfunction "1_1") (pintype "passive"))
      (node (ref "C618") (pin "1") (pinfunction "1_1") (pintype "passive"))
      (node (ref "C619") (pin "1") (pinfunction "1_1") (pintype "passive"))
      (node (ref "C620") (pin "1") (pinfunction "1_1") (pintype "passive"))
      (node (ref "C621") (pin "1") (pinfunction "1_1") (pintype "passive"))
      (node (ref "C622") (pin "1") (pinfunction "1_1") (pintype "passive"))
      (node (ref "C623") (pin "1") (pinfunction "1_1") (pintype "passive"))
      (node (ref "C624") (pin "1") (pinfunction "1_1") (pintype "passive"))
      (node (ref "C625") (pin "1") (pinfunction "1_1") (pintype "passive"))
      (node (ref "C626") (pin "1") (pinfunction "1_1") (pintype "passive"))
      (node (ref "C627") (pin "1") (pinfunction "1_1") (pintype "passive"))
      (node (ref "C628") (pin "1") (pinfunction "1_1") (pintype "passive"))
      (node (ref "C629") (pin "1") (pinfunction "1_1") (pintype "passive"))
      (node (ref "C630") (pin "1") (pinfunction "1_1") (pintype "passive"))
      (node (ref "C632") (pin "2") (pinfunction "2_2") (pintype "passive"))
      (node (ref "C633") (pin "2") (pinfunction "2_2") (pintype "passive"))
      (node (ref "C634") (pin "1") (pinfunction "1_1") (pintype "passive"))
      (node (ref "C635") (pin "2") (pinfunction "2_2") (pintype "passive"))
      (node (ref "IC35") (pin "A1") (pinfunction "VDDQ_A1") (pintype "power_in"))
      (node (ref "IC35") (pin "A8") (pinfunction "VDDQ_A8") (pintype "power_in"))
      (node (ref "IC35") (pin "B2") (pinfunction "VDD_B2") (pintype "power_in"))
      (node (ref "IC35") (pin "C1") (pinfunction "VDDQ_C1") (pintype "power_in"))
      (node (ref "IC35") (pin "C9") (pinfunction "VDDQ_C9") (pintype "power_in"))
      (node (ref "IC35") (pin "D2") (pinfunction "VDDQ_D2") (pintype "power_in"))
      (node (ref "IC35") (pin "D9") (pinfunction "VDD_D9") (pintype "power_in"))
      (node (ref "IC35") (pin "E9") (pinfunction "VDDQ_E9") (pintype "power_in"))
      (node (ref "IC35") (pin "F1") (pinfunction "VDDQ_F1") (pintype "power_in"))
      (node (ref "IC35") (pin "G7") (pinfunction "VDD_G7") (pintype "power_in"))
      (node (ref "IC35") (pin "H2") (pinfunction "VDDQ_H2") (pintype "power_in"))
      (node (ref "IC35") (pin "H9") (pinfunction "VDDQ_H9") (pintype "power_in"))
      (node (ref "IC35") (pin "K2") (pinfunction "VDD_K2") (pintype "power_in"))
      (node (ref "IC35") (pin "K8") (pinfunction "VDD_K8") (pintype "power_in"))
      (node (ref "IC35") (pin "N1") (pinfunction "VDD_N1") (pintype "power_in"))
      (node (ref "IC35") (pin "N9") (pinfunction "VDD_N9") (pintype "power_in"))
      (node (ref "IC35") (pin "R1") (pinfunction "VDD_R1") (pintype "power_in"))
      (node (ref "IC35") (pin "R9") (pinfunction "VDD_R9") (pintype "power_in"))
      (node (ref "IC36") (pin "A1") (pinfunction "VDDQ_A1") (pintype "power_in"))
      (node (ref "IC36") (pin "A8") (pinfunction "VDDQ_A8") (pintype "power_in"))
      (node (ref "IC36") (pin "B2") (pinfunction "VDD_B2") (pintype "power_in"))
      (node (ref "IC36") (pin "C1") (pinfunction "VDDQ_C1") (pintype "power_in"))
      (node (ref "IC36") (pin "C9") (pinfunction "VDDQ_C9") (pintype "power_in"))
      (node (ref "IC36") (pin "D2") (pinfunction "VDDQ_D2") (pintype "power_in"))
      (node (ref "IC36") (pin "D9") (pinfunction "VDD_D9") (pintype "power_in"))
      (node (ref "IC36") (pin "E9") (pinfunction "VDDQ_E9") (pintype "power_in"))
      (node (ref "IC36") (pin "F1") (pinfunction "VDDQ_F1") (pintype "power_in"))
      (node (ref "IC36") (pin "G7") (pinfunction "VDD_G7") (pintype "power_in"))
      (node (ref "IC36") (pin "H2") (pinfunction "VDDQ_H2") (pintype "power_in"))
      (node (ref "IC36") (pin "H9") (pinfunction "VDDQ_H9") (pintype "power_in"))
      (node (ref "IC36") (pin "K2") (pinfunction "VDD_K2") (pintype "power_in"))
      (node (ref "IC36") (pin "K8") (pinfunction "VDD_K8") (pintype "power_in"))
      (node (ref "IC36") (pin "N1") (pinfunction "VDD_N1") (pintype "power_in"))
      (node (ref "IC36") (pin "N9") (pinfunction "VDD_N9") (pintype "power_in"))
      (node (ref "IC36") (pin "R1") (pinfunction "VDD_R1") (pintype "power_in"))
      (node (ref "IC36") (pin "R9") (pinfunction "VDD_R9") (pintype "power_in"))
    )
    (net (code "80") (name "VTT_DDR3_BOT") (class "Default")
      (node (ref "C594") (pin "1") (pinfunction "1_1") (pintype "passive"))
      (node (ref "C594") (pin "2") (pinfunction "2_2") (pintype "passive"))
      (node (ref "C594") (pin "3") (pinfunction "3_3") (pintype "passive"))
      (node (ref "C594") (pin "4") (pinfunction "4_4") (pintype "passive"))
      (node (ref "C603") (pin "1") (pinfunction "1_1") (pintype "passive"))
      (node (ref "C603") (pin "2") (pinfunction "2_2") (pintype "passive"))
      (node (ref "C603") (pin "3") (pinfunction "3_3") (pintype "passive"))
      (node (ref "C603") (pin "4") (pinfunction "4_4") (pintype "passive"))
      (node (ref "C611") (pin "1") (pinfunction "1_1") (pintype "passive"))
      (node (ref "C611") (pin "2") (pinfunction "2_2") (pintype "passive"))
      (node (ref "C611") (pin "3") (pinfunction "3_3") (pintype "passive"))
      (node (ref "C611") (pin "4") (pinfunction "4_4") (pintype "passive"))
      (node (ref "R200") (pin "10") (pinfunction "10_10") (pintype "passive"))
      (node (ref "R200") (pin "11") (pinfunction "11_11") (pintype "passive"))
      (node (ref "R200") (pin "12") (pinfunction "12_12") (pintype "passive"))
      (node (ref "R200") (pin "13") (pinfunction "13_13") (pintype "passive"))
      (node (ref "R200") (pin "14") (pinfunction "14_14") (pintype "passive"))
      (node (ref "R200") (pin "15") (pinfunction "15_15") (pintype "passive"))
      (node (ref "R200") (pin "16") (pinfunction "16_16") (pintype "passive"))
      (node (ref "R200") (pin "9") (pinfunction "9_9") (pintype "passive"))
      (node (ref "R203") (pin "10") (pinfunction "10_10") (pintype "passive"))
      (node (ref "R203") (pin "11") (pinfunction "11_11") (pintype "passive"))
      (node (ref "R203") (pin "12") (pinfunction "12_12") (pintype "passive"))
      (node (ref "R203") (pin "13") (pinfunction "13_13") (pintype "passive"))
      (node (ref "R203") (pin "14") (pinfunction "14_14") (pintype "passive"))
      (node (ref "R203") (pin "15") (pinfunction "15_15") (pintype "passive"))
      (node (ref "R203") (pin "16") (pinfunction "16_16") (pintype "passive"))
      (node (ref "R203") (pin "9") (pinfunction "9_9") (pintype "passive"))
      (node (ref "R205") (pin "10") (pinfunction "10_10") (pintype "passive"))
      (node (ref "R205") (pin "11") (pinfunction "11_11") (pintype "passive"))
      (node (ref "R205") (pin "12") (pinfunction "12_12") (pintype "passive"))
      (node (ref "R205") (pin "13") (pinfunction "13_13") (pintype "passive"))
      (node (ref "R205") (pin "14") (pinfunction "14_14") (pintype "passive"))
      (node (ref "R205") (pin "15") (pinfunction "15_15") (pintype "passive"))
      (node (ref "R205") (pin "16") (pinfunction "16_16") (pintype "passive"))
      (node (ref "R205") (pin "9") (pinfunction "9_9") (pintype "passive"))
    )
    (net (code "81") (name "unconnected-(IC35B-NC-PadJ1)") (class "Default")
      (node (ref "IC35") (pin "J1") (pinfunction "NC_J1") (pintype "passive+no_connect"))
    )
    (net (code "82") (name "unconnected-(IC35B-NC-PadJ9)") (class "Default")
      (node (ref "IC35") (pin "J9") (pinfunction "NC_J9") (pintype "passive+no_connect"))
    )
    (net (code "83") (name "unconnected-(IC35B-NC-PadL1)") (class "Default")
      (node (ref "IC35") (pin "L1") (pinfunction "NC_L1") (pintype "passive+no_connect"))
    )
    (net (code "84") (name "unconnected-(IC35B-NC-PadL9)") (class "Default")
      (node (ref "IC35") (pin "L9") (pinfunction "NC_L9") (pintype "passive+no_connect"))
    )
    (net (code "85") (name "unconnected-(IC35B-NC-PadM7)") (class "Default")
      (node (ref "IC35") (pin "M7") (pinfunction "NC_M7") (pintype "passive+no_connect"))
    )
    (net (code "86") (name "unconnected-(IC35B-NC-PadT7)") (class "Default")
      (node (ref "IC35") (pin "T7") (pinfunction "NC_T7") (pintype "passive+no_connect"))
    )
    (net (code "87") (name "unconnected-(IC36B-NC-PadJ1)") (class "Default")
      (node (ref "IC36") (pin "J1") (pinfunction "NC_J1") (pintype "passive+no_connect"))
    )
    (net (code "88") (name "unconnected-(IC36B-NC-PadJ9)") (class "Default")
      (node (ref "IC36") (pin "J9") (pinfunction "NC_J9") (pintype "passive+no_connect"))
    )
    (net (code "89") (name "unconnected-(IC36B-NC-PadL1)") (class "Default")
      (node (ref "IC36") (pin "L1") (pinfunction "NC_L1") (pintype "passive+no_connect"))
    )
    (net (code "90") (name "unconnected-(IC36B-NC-PadL9)") (class "Default")
      (node (ref "IC36") (pin "L9") (pinfunction "NC_L9") (pintype "passive+no_connect"))
    )
    (net (code "91") (name "unconnected-(IC36B-NC-PadM7)") (class "Default")
      (node (ref "IC36") (pin "M7") (pinfunction "NC_M7") (pintype "passive+no_connect"))
    )
    (net (code "92") (name "unconnected-(IC36B-NC-PadT7)") (class "Default")
      (node (ref "IC36") (pin "T7") (pinfunction "NC_T7") (pintype "passive+no_connect"))
    )
    (net (code "93") (name "unconnected-(R200-Pad7)") (class "Default")
      (node (ref "R200") (pin "7") (pinfunction "7_7") (pintype "passive+no_connect"))
    )
  )
)
